# Power_Neg.net
KiCad netlist of a schematic drawn in Altium Designer
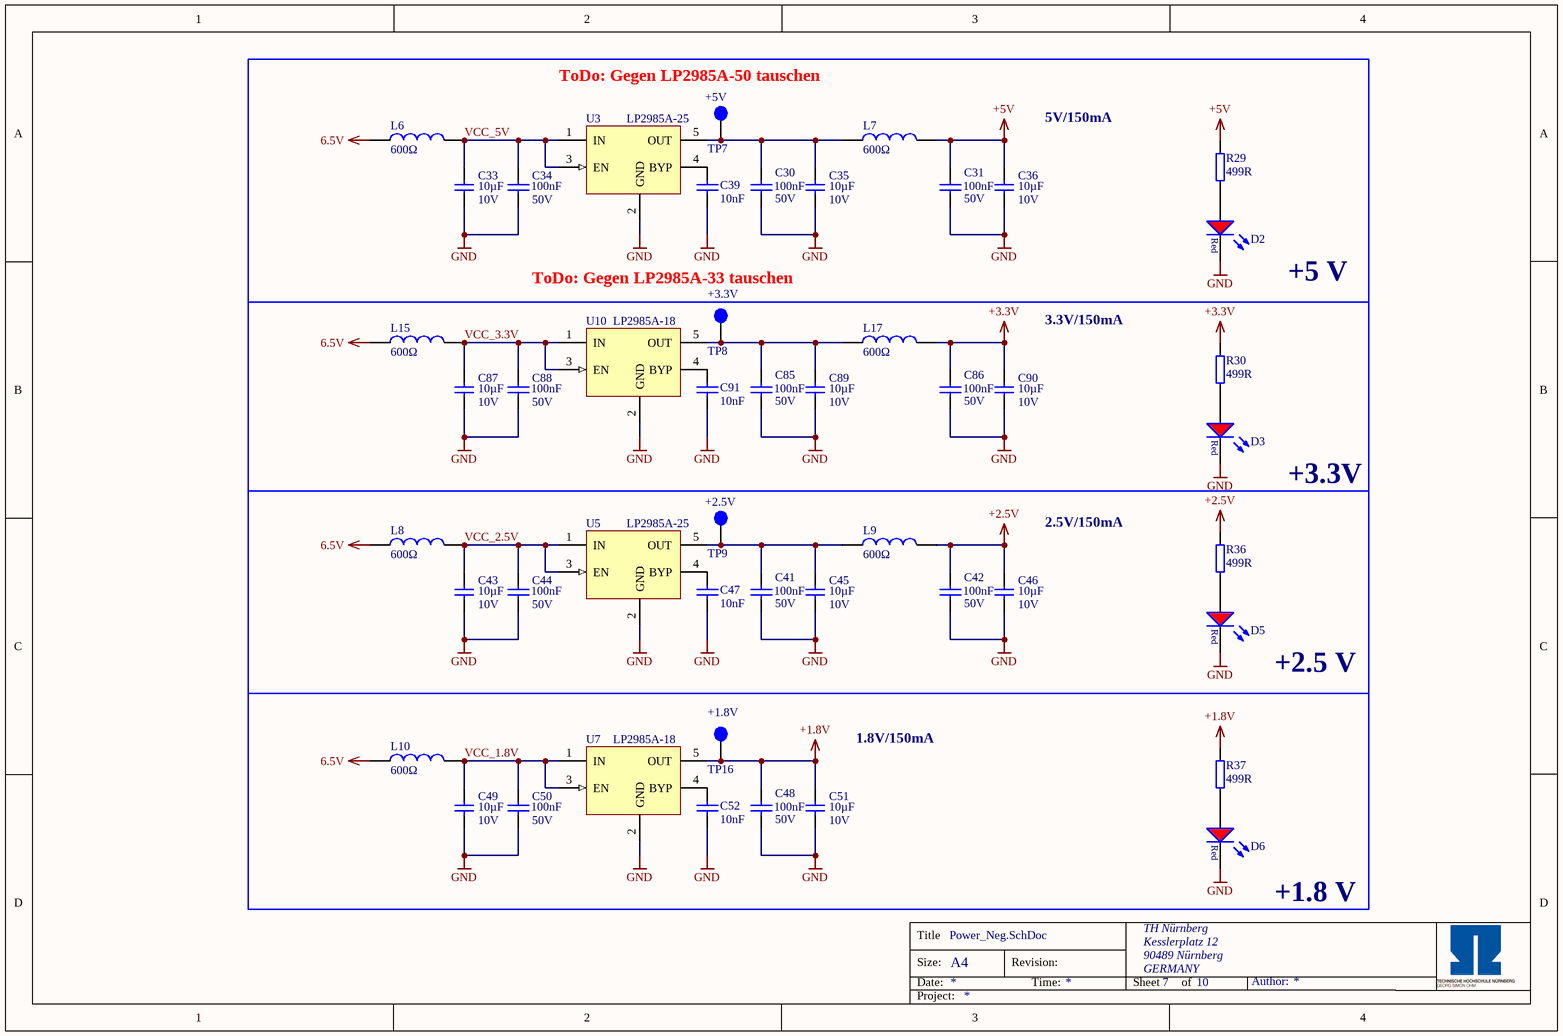
[diagram p0: Power_Neg.SchDoc]

(export (version "E")
  (design (tool "Eeschema 10.0.6"))
  (components
    (comp (ref "C30")
      (value "100nF")
      (footprint "CAPC1608X07N")
      (fields
        (field (name "MF") "Yageo")
        (field (name "MPN") "CC0603KRX7R9BB104")
        (field (name "VOLTAGE") "50V")
      )
      (libsource (lib "UltraZohm_ADC") (part "Cap_0603"))
    )
    (comp (ref "C31")
      (value "100nF")
      (footprint "CAPC1608X07N")
      (fields
        (field (name "MF") "Yageo")
        (field (name "MPN") "CC0603KRX7R9BB104")
        (field (name "VOLTAGE") "50V")
      )
      (libsource (lib "UltraZohm_ADC") (part "Cap_0603"))
    )
    (comp (ref "C33")
      (value "10µF")
      (footprint "C_1206")
      (description "Capacitor 1206")
      (fields
        (field (name "TOLERANCE") "10%")
        (field (name "MF") "Samsung Electro-Mechanics")
        (field (name "VOLTAGE") "10V")
        (field (name "CREATED") "2020_09_17_Liegmann")
      )
      (libsource (lib "UltraZohm_ADC") (part "C_1206"))
    )
    (comp (ref "C34")
      (value "100nF")
      (footprint "CAPC1608X07N")
      (fields
        (field (name "MF") "Yageo")
        (field (name "MPN") "CC0603KRX7R9BB104")
        (field (name "VOLTAGE") "50V")
        (field (name "TOLERANCE") "10%")
      )
      (libsource (lib "UltraZohm_ADC") (part "Cap_0603"))
    )
    (comp (ref "C35")
      (value "10µF")
      (footprint "C_1206")
      (description "Capacitor 1206")
      (fields
        (field (name "TOLERANCE") "10%")
        (field (name "MF") "Samsung Electro-Mechanics")
        (field (name "VOLTAGE") "10V")
        (field (name "CREATED") "2020_09_17_Liegmann")
      )
      (libsource (lib "UltraZohm_ADC") (part "C_1206"))
    )
    (comp (ref "C36")
      (value "10µF")
      (footprint "C_1206")
      (description "Capacitor 1206")
      (fields
        (field (name "TOLERANCE") "10%")
        (field (name "MF") "Samsung Electro-Mechanics")
        (field (name "VOLTAGE") "10V")
        (field (name "CREATED") "2020_09_17_Liegmann")
      )
      (libsource (lib "UltraZohm_ADC") (part "C_1206"))
    )
    (comp (ref "C39")
      (value "10nF")
      (footprint "CAPC1608X07N")
      (fields (field (name "MF") "Würth") (field (name "MPN") "885012206065") (field (name "VOLTAGE") "25V"))
      (libsource (lib "UltraZohm_ADC") (part "Cap_0603"))
    )
    (comp (ref "C41")
      (value "100nF")
      (footprint "CAPC1608X07N")
      (fields
        (field (name "MF") "Yageo")
        (field (name "MPN") "CC0603KRX7R9BB104")
        (field (name "VOLTAGE") "50V")
      )
      (libsource (lib "UltraZohm_ADC") (part "Cap_0603"))
    )
    (comp (ref "C42")
      (value "100nF")
      (footprint "CAPC1608X07N")
      (fields
        (field (name "MF") "Yageo")
        (field (name "MPN") "CC0603KRX7R9BB104")
        (field (name "VOLTAGE") "50V")
      )
      (libsource (lib "UltraZohm_ADC") (part "Cap_0603"))
    )
    (comp (ref "C43")
      (value "10µF")
      (footprint "C_1206")
      (description "Capacitor 1206")
      (fields
        (field (name "TOLERANCE") "10%")
        (field (name "MF") "Samsung Electro-Mechanics")
        (field (name "VOLTAGE") "10V")
        (field (name "CREATED") "2020_09_17_Liegmann")
      )
      (libsource (lib "UltraZohm_ADC") (part "C_1206"))
    )
    (comp (ref "C44")
      (value "100nF")
      (footprint "CAPC1608X07N")
      (fields
        (field (name "MF") "Yageo")
        (field (name "MPN") "CC0603KRX7R9BB104")
        (field (name "VOLTAGE") "50V")
        (field (name "TOLERANCE") "10%")
      )
      (libsource (lib "UltraZohm_ADC") (part "Cap_0603"))
    )
    (comp (ref "C45")
      (value "10µF")
      (footprint "C_1206")
      (description "Capacitor 1206")
      (fields
        (field (name "TOLERANCE") "10%")
        (field (name "MF") "Samsung Electro-Mechanics")
        (field (name "VOLTAGE") "10V")
        (field (name "CREATED") "2020_09_17_Liegmann")
      )
      (libsource (lib "UltraZohm_ADC") (part "C_1206"))
    )
    (comp (ref "C46")
      (value "10µF")
      (footprint "C_1206")
      (description "Capacitor 1206")
      (fields
        (field (name "TOLERANCE") "10%")
        (field (name "MF") "Samsung Electro-Mechanics")
        (field (name "VOLTAGE") "10V")
        (field (name "CREATED") "2020_09_17_Liegmann")
      )
      (libsource (lib "UltraZohm_ADC") (part "C_1206"))
    )
    (comp (ref "C47")
      (value "10nF")
      (footprint "CAPC1608X07N")
      (fields (field (name "MF") "Würth") (field (name "MPN") "885012206065") (field (name "VOLTAGE") "25V"))
      (libsource (lib "UltraZohm_ADC") (part "Cap_0603"))
    )
    (comp (ref "C48")
      (value "100nF")
      (footprint "CAPC1608X07N")
      (fields
        (field (name "MF") "Yageo")
        (field (name "MPN") "CC0603KRX7R9BB104")
        (field (name "VOLTAGE") "50V")
      )
      (libsource (lib "UltraZohm_ADC") (part "Cap_0603"))
    )
    (comp (ref "C49")
      (value "10µF")
      (footprint "C_1206")
      (description "Capacitor 1206")
      (fields
        (field (name "TOLERANCE") "10%")
        (field (name "MF") "Samsung Electro-Mechanics")
        (field (name "VOLTAGE") "10V")
        (field (name "CREATED") "2020_09_17_Liegmann")
      )
      (libsource (lib "UltraZohm_ADC") (part "C_1206"))
    )
    (comp (ref "C50")
      (value "100nF")
      (footprint "CAPC1608X07N")
      (fields
        (field (name "MF") "Yageo")
        (field (name "MPN") "CC0603KRX7R9BB104")
        (field (name "VOLTAGE") "50V")
        (field (name "TOLERANCE") "10%")
      )
      (libsource (lib "UltraZohm_ADC") (part "Cap_0603"))
    )
    (comp (ref "C51")
      (value "10µF")
      (footprint "C_1206")
      (description "Capacitor 1206")
      (fields
        (field (name "TOLERANCE") "10%")
        (field (name "MF") "Samsung Electro-Mechanics")
        (field (name "VOLTAGE") "10V")
        (field (name "CREATED") "2020_09_17_Liegmann")
      )
      (libsource (lib "UltraZohm_ADC") (part "C_1206"))
    )
    (comp (ref "C52")
      (value "10nF")
      (footprint "CAPC1608X07N")
      (fields (field (name "MF") "Würth") (field (name "MPN") "885012206065") (field (name "VOLTAGE") "25V"))
      (libsource (lib "UltraZohm_ADC") (part "Cap_0603"))
    )
    (comp (ref "C85")
      (value "100nF")
      (footprint "CAPC1608X07N")
      (fields
        (field (name "MF") "Yageo")
        (field (name "MPN") "CC0603KRX7R9BB104")
        (field (name "VOLTAGE") "50V")
      )
      (libsource (lib "UltraZohm_ADC") (part "Cap_0603"))
    )
    (comp (ref "C86")
      (value "100nF")
      (footprint "CAPC1608X07N")
      (fields
        (field (name "MF") "Yageo")
        (field (name "MPN") "CC0603KRX7R9BB104")
        (field (name "VOLTAGE") "50V")
      )
      (libsource (lib "UltraZohm_ADC") (part "Cap_0603"))
    )
    (comp (ref "C87")
      (value "10µF")
      (footprint "C_1206")
      (description "Capacitor 1206")
      (fields
        (field (name "TOLERANCE") "10%")
        (field (name "MF") "Samsung Electro-Mechanics")
        (field (name "VOLTAGE") "10V")
        (field (name "CREATED") "2020_09_17_Liegmann")
      )
      (libsource (lib "UltraZohm_ADC") (part "C_1206"))
    )
    (comp (ref "C88")
      (value "100nF")
      (footprint "CAPC1608X07N")
      (fields
        (field (name "MF") "Yageo")
        (field (name "MPN") "CC0603KRX7R9BB104")
        (field (name "VOLTAGE") "50V")
        (field (name "TOLERANCE") "10%")
      )
      (libsource (lib "UltraZohm_ADC") (part "Cap_0603"))
    )
    (comp (ref "C89")
      (value "10µF")
      (footprint "C_1206")
      (description "Capacitor 1206")
      (fields
        (field (name "TOLERANCE") "10%")
        (field (name "MF") "Samsung Electro-Mechanics")
        (field (name "VOLTAGE") "10V")
        (field (name "CREATED") "2020_09_17_Liegmann")
      )
      (libsource (lib "UltraZohm_ADC") (part "C_1206"))
    )
    (comp (ref "C90")
      (value "10µF")
      (footprint "C_1206")
      (description "Capacitor 1206")
      (fields
        (field (name "TOLERANCE") "10%")
        (field (name "MF") "Samsung Electro-Mechanics")
        (field (name "VOLTAGE") "10V")
        (field (name "CREATED") "2020_09_17_Liegmann")
      )
      (libsource (lib "UltraZohm_ADC") (part "C_1206"))
    )
    (comp (ref "C91")
      (value "10nF")
      (footprint "CAPC1608X07N")
      (fields (field (name "MF") "Würth") (field (name "MPN") "885012206065") (field (name "VOLTAGE") "25V"))
      (libsource (lib "UltraZohm_ADC") (part "Cap_0603"))
    )
    (comp (ref "D2")
      (value "150060RS75000")
      (footprint "WL-SMCW_0603")
      (description "WL-SMCW SMD Mono-color Chip LED Waterclear, size 0603, Red, 2 V, 140°")
      (fields (field (name "MF") "Wuerth Elektronik") (field (name "CREATED") "2018_09_06_AGeiger"))
      (libsource (lib "UltraZohm_ADC") (part "LED_Red_0603"))
    )
    (comp (ref "D3")
      (value "150060RS75000")
      (footprint "WL-SMCW_0603")
      (description "WL-SMCW SMD Mono-color Chip LED Waterclear, size 0603, Red, 2 V, 140°")
      (fields (field (name "MF") "Wuerth Elektronik") (field (name "CREATED") "2018_09_06_AGeiger"))
      (libsource (lib "UltraZohm_ADC") (part "LED_Red_0603"))
    )
    (comp (ref "D5")
      (value "150060RS75000")
      (footprint "WL-SMCW_0603")
      (description "WL-SMCW SMD Mono-color Chip LED Waterclear, size 0603, Red, 2 V, 140°")
      (fields (field (name "MF") "Wuerth Elektronik") (field (name "CREATED") "2018_09_06_AGeiger"))
      (libsource (lib "UltraZohm_ADC") (part "LED_Red_0603"))
    )
    (comp (ref "D6")
      (value "150060RS75000")
      (footprint "WL-SMCW_0603")
      (description "WL-SMCW SMD Mono-color Chip LED Waterclear, size 0603, Red, 2 V, 140°")
      (fields (field (name "MF") "Wuerth Elektronik") (field (name "CREATED") "2018_09_06_AGeiger"))
      (libsource (lib "UltraZohm_ADC") (part "LED_Red_0603"))
    )
    (comp (ref "L6")
      (value "600Ω")
      (footprint "WE-CBF_0805_High Current")
      (description "WE-CBF SMD EMI Suppression Ferrite Bead, 0805, 600Ω")
      (fields (field (name "MF") "Wurth Elektronik") (field (name "MPN") "742792040"))
      (libsource (lib "UltraZohm_ADC") (part "WE-CBF, 742792040"))
    )
    (comp (ref "L7")
      (value "600Ω")
      (footprint "WE-CBF_0805_High Current")
      (description "WE-CBF SMD EMI Suppression Ferrite Bead, 0805, 600Ω")
      (fields (field (name "MF") "Wurth Elektronik") (field (name "MPN") "742792040"))
      (libsource (lib "UltraZohm_ADC") (part "WE-CBF, 742792040"))
    )
    (comp (ref "L8")
      (value "600Ω")
      (footprint "WE-CBF_0805_High Current")
      (description "WE-CBF SMD EMI Suppression Ferrite Bead, 0805, 600Ω")
      (fields (field (name "MF") "Wurth Elektronik") (field (name "MPN") "742792040"))
      (libsource (lib "UltraZohm_ADC") (part "WE-CBF, 742792040"))
    )
    (comp (ref "L9")
      (value "600Ω")
      (footprint "WE-CBF_0805_High Current")
      (description "WE-CBF SMD EMI Suppression Ferrite Bead, 0805, 600Ω")
      (fields (field (name "MF") "Wurth Elektronik") (field (name "MPN") "742792040"))
      (libsource (lib "UltraZohm_ADC") (part "WE-CBF, 742792040"))
    )
    (comp (ref "L10")
      (value "600Ω")
      (footprint "WE-CBF_0805_High Current")
      (description "WE-CBF SMD EMI Suppression Ferrite Bead, 0805, 600Ω")
      (fields (field (name "MF") "Wurth Elektronik") (field (name "MPN") "742792040"))
      (libsource (lib "UltraZohm_ADC") (part "WE-CBF, 742792040"))
    )
    (comp (ref "L15")
      (value "600Ω")
      (footprint "WE-CBF_0805_High Current")
      (description "WE-CBF SMD EMI Suppression Ferrite Bead, 0805, 600Ω")
      (fields (field (name "MF") "Wurth Elektronik") (field (name "MPN") "742792040"))
      (libsource (lib "UltraZohm_ADC") (part "WE-CBF, 742792040"))
    )
    (comp (ref "L17")
      (value "600Ω")
      (footprint "WE-CBF_0805_High Current")
      (description "WE-CBF SMD EMI Suppression Ferrite Bead, 0805, 600Ω")
      (fields (field (name "MF") "Wurth Elektronik") (field (name "MPN") "742792040"))
      (libsource (lib "UltraZohm_ADC") (part "WE-CBF, 742792040"))
    )
    (comp (ref "R29")
      (value "499R")
      (footprint "RESC1608X06N")
      (fields (field (name "MF") "Vishay / Dale") (field (name "MPN") "CRCW0603499RFKEAC"))
      (libsource (lib "UltraZohm_ADC") (part "R_0603"))
    )
    (comp (ref "R30")
      (value "499R")
      (footprint "RESC1608X06N")
      (fields (field (name "MF") "Vishay / Dale") (field (name "MPN") "CRCW0603499RFKEAC"))
      (libsource (lib "UltraZohm_ADC") (part "R_0603"))
    )
    (comp (ref "R36")
      (value "499R")
      (footprint "RESC1608X06N")
      (fields (field (name "MF") "Vishay / Dale") (field (name "MPN") "CRCW0603499RFKEAC"))
      (libsource (lib "UltraZohm_ADC") (part "R_0603"))
    )
    (comp (ref "R37")
      (value "499R")
      (footprint "RESC1608X06N")
      (fields (field (name "MF") "Vishay / Dale") (field (name "MPN") "CRCW0603499RFKEAC"))
      (libsource (lib "UltraZohm_ADC") (part "R_0603"))
    )
    (comp (ref "TP7")
      (value "+5V")
      (footprint "TP_1mm")
      (description "Testpoint 1mm")
      (fields (field (name "CREATED") "2018_06_25_AGeiger"))
      (libsource (lib "UltraZOhm_CarrierBoard") (part "TP_1mm"))
    )
    (comp (ref "TP8")
      (value "+3.3V")
      (footprint "TP_1mm")
      (description "Testpoint 1mm")
      (fields (field (name "CREATED") "2018_06_25_AGeiger"))
      (libsource (lib "UltraZOhm_CarrierBoard") (part "TP_1mm"))
    )
    (comp (ref "TP9")
      (value "+2.5V")
      (footprint "TP_1mm")
      (description "Testpoint 1mm")
      (fields (field (name "CREATED") "2018_06_25_AGeiger"))
      (libsource (lib "UltraZOhm_CarrierBoard") (part "TP_1mm"))
    )
    (comp (ref "TP16")
      (value "+1.8V")
      (footprint "TP_1mm")
      (description "Testpoint 1mm")
      (fields (field (name "CREATED") "2018_06_25_AGeiger"))
      (libsource (lib "UltraZOhm_CarrierBoard") (part "TP_1mm"))
    )
    (comp (ref "U3")
      (value "LP2985A-25")
      (footprint "SOT95P250X110-5N")
      (description "150mA, LDO, Vout = 2.5V, Vin,max = 16V")
      (fields (field (name "MF") "Texas Instruments"))
      (libsource (lib "UltraZohm_ADC") (part "LP2985A-25"))
    )
    (comp (ref "U5")
      (value "LP2985A-25")
      (footprint "SOT95P250X110-5N")
      (description "150mA, LDO, Vout = 2.5V, Vin,max = 16V")
      (fields (field (name "MF") "Texas Instruments"))
      (libsource (lib "UltraZohm_ADC") (part "LP2985A-25"))
    )
    (comp (ref "U7")
      (value "LP2985A-18")
      (footprint "SOT95P250X110-5N")
      (description "150mA, LDO, Vout = 1.8V , Vin,max = 16V")
      (libsource (lib "UltraZohm_ADC") (part "LP2985A-18"))
    )
    (comp (ref "U10")
      (value "LP2985A-18")
      (footprint "SOT95P250X110-5N")
      (description "150mA, LDO, Vout = 1.8V , Vin,max = 16V")
      (libsource (lib "UltraZohm_ADC") (part "LP2985A-18"))
    )
  )
  (nets
    (net (code "1") (name "+1.8V") (class "Default")
      (node (ref "C48") (pin "1") (pinfunction "1_1") (pintype "passive"))
      (node (ref "C51") (pin "2") (pinfunction "2_2") (pintype "passive"))
      (node (ref "R37") (pin "2") (pintype "passive"))
      (node (ref "TP16") (pin "1") (pintype "passive"))
      (node (ref "U7") (pin "5") (pinfunction "OUT_5") (pintype "power_in"))
    )
    (net (code "2") (name "+2.5V") (class "Default")
      (node (ref "C42") (pin "1") (pinfunction "1_1") (pintype "passive"))
      (node (ref "C46") (pin "2") (pinfunction "2_2") (pintype "passive"))
      (node (ref "L9") (pin "2") (pinfunction "2_2") (pintype "passive"))
      (node (ref "R36") (pin "2") (pintype "passive"))
    )
    (net (code "3") (name "+3.3V") (class "Default")
      (node (ref "C86") (pin "1") (pinfunction "1_1") (pintype "passive"))
      (node (ref "C90") (pin "2") (pinfunction "2_2") (pintype "passive"))
      (node (ref "L17") (pin "2") (pinfunction "2_2") (pintype "passive"))
      (node (ref "R30") (pin "2") (pintype "passive"))
    )
    (net (code "4") (name "+5V") (class "Default")
      (node (ref "C31") (pin "1") (pinfunction "1_1") (pintype "passive"))
      (node (ref "C36") (pin "2") (pinfunction "2_2") (pintype "passive"))
      (node (ref "L7") (pin "2") (pinfunction "2_2") (pintype "passive"))
      (node (ref "R29") (pin "2") (pintype "passive"))
    )
    (net (code "5") (name "/VCC_1.8V") (class "Default")
      (node (ref "C49") (pin "2") (pinfunction "2_2") (pintype "passive"))
      (node (ref "C50") (pin "1") (pinfunction "1_1") (pintype "passive"))
      (node (ref "L10") (pin "2") (pinfunction "2_2") (pintype "passive"))
      (node (ref "U7") (pin "1") (pinfunction "IN_1") (pintype "power_in"))
      (node (ref "U7") (pin "3") (pinfunction "EN_3") (pintype "input"))
    )
    (net (code "6") (name "/VCC_2.5V") (class "Default")
      (node (ref "C43") (pin "2") (pinfunction "2_2") (pintype "passive"))
      (node (ref "C44") (pin "1") (pinfunction "1_1") (pintype "passive"))
      (node (ref "L8") (pin "2") (pinfunction "2_2") (pintype "passive"))
      (node (ref "U5") (pin "1") (pinfunction "IN_1") (pintype "power_in"))
      (node (ref "U5") (pin "3") (pinfunction "EN_3") (pintype "input"))
    )
    (net (code "7") (name "/VCC_3.3V") (class "Default")
      (node (ref "C87") (pin "2") (pinfunction "2_2") (pintype "passive"))
      (node (ref "C88") (pin "1") (pinfunction "1_1") (pintype "passive"))
      (node (ref "L15") (pin "2") (pinfunction "2_2") (pintype "passive"))
      (node (ref "U10") (pin "1") (pinfunction "IN_1") (pintype "power_in"))
      (node (ref "U10") (pin "3") (pinfunction "EN_3") (pintype "input"))
    )
    (net (code "8") (name "/VCC_5V") (class "Default")
      (node (ref "C33") (pin "2") (pinfunction "2_2") (pintype "passive"))
      (node (ref "C34") (pin "1") (pinfunction "1_1") (pintype "passive"))
      (node (ref "L6") (pin "2") (pinfunction "2_2") (pintype "passive"))
      (node (ref "U3") (pin "1") (pinfunction "IN_1") (pintype "power_in"))
      (node (ref "U3") (pin "3") (pinfunction "EN_3") (pintype "input"))
    )
    (net (code "9") (name "6.5V") (class "Default")
      (node (ref "L10") (pin "1") (pinfunction "1_1") (pintype "passive"))
      (node (ref "L15") (pin "1") (pinfunction "1_1") (pintype "passive"))
      (node (ref "L6") (pin "1") (pinfunction "1_1") (pintype "passive"))
      (node (ref "L8") (pin "1") (pinfunction "1_1") (pintype "passive"))
    )
    (net (code "10") (name "GND") (class "Default")
      (node (ref "C30") (pin "2") (pinfunction "2_2") (pintype "passive"))
      (node (ref "C31") (pin "2") (pinfunction "2_2") (pintype "passive"))
      (node (ref "C33") (pin "1") (pinfunction "1_1") (pintype "passive"))
      (node (ref "C34") (pin "2") (pinfunction "2_2") (pintype "passive"))
      (node (ref "C35") (pin "1") (pinfunction "1_1") (pintype "passive"))
      (node (ref "C36") (pin "1") (pinfunction "1_1") (pintype "passive"))
      (node (ref "C39") (pin "1") (pinfunction "1_1") (pintype "passive"))
      (node (ref "C41") (pin "2") (pinfunction "2_2") (pintype "passive"))
      (node (ref "C42") (pin "2") (pinfunction "2_2") (pintype "passive"))
      (node (ref "C43") (pin "1") (pinfunction "1_1") (pintype "passive"))
      (node (ref "C44") (pin "2") (pinfunction "2_2") (pintype "passive"))
      (node (ref "C45") (pin "1") (pinfunction "1_1") (pintype "passive"))
      (node (ref "C46") (pin "1") (pinfunction "1_1") (pintype "passive"))
      (node (ref "C47") (pin "1") (pinfunction "1_1") (pintype "passive"))
      (node (ref "C48") (pin "2") (pinfunction "2_2") (pintype "passive"))
      (node (ref "C49") (pin "1") (pinfunction "1_1") (pintype "passive"))
      (node (ref "C50") (pin "2") (pinfunction "2_2") (pintype "passive"))
      (node (ref "C51") (pin "1") (pinfunction "1_1") (pintype "passive"))
      (node (ref "C52") (pin "1") (pinfunction "1_1") (pintype "passive"))
      (node (ref "C85") (pin "2") (pinfunction "2_2") (pintype "passive"))
      (node (ref "C86") (pin "2") (pinfunction "2_2") (pintype "passive"))
      (node (ref "C87") (pin "1") (pinfunction "1_1") (pintype "passive"))
      (node (ref "C88") (pin "2") (pinfunction "2_2") (pintype "passive"))
      (node (ref "C89") (pin "1") (pinfunction "1_1") (pintype "passive"))
      (node (ref "C90") (pin "1") (pinfunction "1_1") (pintype "passive"))
      (node (ref "C91") (pin "1") (pinfunction "1_1") (pintype "passive"))
      (node (ref "D2") (pin "1") (pinfunction "K_1") (pintype "passive"))
      (node (ref "D3") (pin "1") (pinfunction "K_1") (pintype "passive"))
      (node (ref "D5") (pin "1") (pinfunction "K_1") (pintype "passive"))
      (node (ref "D6") (pin "1") (pinfunction "K_1") (pintype "passive"))
      (node (ref "U10") (pin "2") (pinfunction "GND_2") (pintype "power_in"))
      (node (ref "U3") (pin "2") (pinfunction "GND_2") (pintype "power_in"))
      (node (ref "U5") (pin "2") (pinfunction "GND_2") (pintype "power_in"))
      (node (ref "U7") (pin "2") (pinfunction "GND_2") (pintype "power_in"))
    )
    (net (code "11") (name "Net-(D2-A)") (class "Default")
      (node (ref "D2") (pin "2") (pinfunction "A_2") (pintype "passive"))
      (node (ref "R29") (pin "1") (pintype "passive"))
    )
    (net (code "12") (name "Net-(D3-A)") (class "Default")
      (node (ref "D3") (pin "2") (pinfunction "A_2") (pintype "passive"))
      (node (ref "R30") (pin "1") (pintype "passive"))
    )
    (net (code "13") (name "Net-(D5-A)") (class "Default")
      (node (ref "D5") (pin "2") (pinfunction "A_2") (pintype "passive"))
      (node (ref "R36") (pin "1") (pintype "passive"))
    )
    (net (code "14") (name "Net-(D6-A)") (class "Default")
      (node (ref "D6") (pin "2") (pinfunction "A_2") (pintype "passive"))
      (node (ref "R37") (pin "1") (pintype "passive"))
    )
    (net (code "15") (name "Net-(U3-BYP)") (class "Default")
      (node (ref "C39") (pin "2") (pinfunction "2_2") (pintype "passive"))
      (node (ref "U3") (pin "4") (pinfunction "BYP_4") (pintype "passive"))
    )
    (net (code "16") (name "Net-(U3-OUT)") (class "Default")
      (node (ref "C30") (pin "1") (pinfunction "1_1") (pintype "passive"))
      (node (ref "C35") (pin "2") (pinfunction "2_2") (pintype "passive"))
      (node (ref "L7") (pin "1") (pinfunction "1_1") (pintype "passive"))
      (node (ref "TP7") (pin "1") (pintype "passive"))
      (node (ref "U3") (pin "5") (pinfunction "OUT_5") (pintype "power_in"))
    )
    (net (code "17") (name "Net-(U5-BYP)") (class "Default")
      (node (ref "C47") (pin "2") (pinfunction "2_2") (pintype "passive"))
      (node (ref "U5") (pin "4") (pinfunction "BYP_4") (pintype "passive"))
    )
    (net (code "18") (name "Net-(U5-OUT)") (class "Default")
      (node (ref "C41") (pin "1") (pinfunction "1_1") (pintype "passive"))
      (node (ref "C45") (pin "2") (pinfunction "2_2") (pintype "passive"))
      (node (ref "L9") (pin "1") (pinfunction "1_1") (pintype "passive"))
      (node (ref "TP9") (pin "1") (pintype "passive"))
      (node (ref "U5") (pin "5") (pinfunction "OUT_5") (pintype "power_in"))
    )
    (net (code "19") (name "Net-(U7-BYP)") (class "Default")
      (node (ref "C52") (pin "2") (pinfunction "2_2") (pintype "passive"))
      (node (ref "U7") (pin "4") (pinfunction "BYP_4") (pintype "passive"))
    )
    (net (code "20") (name "Net-(U10-BYP)") (class "Default")
      (node (ref "C91") (pin "2") (pinfunction "2_2") (pintype "passive"))
      (node (ref "U10") (pin "4") (pinfunction "BYP_4") (pintype "passive"))
    )
    (net (code "21") (name "Net-(U10-OUT)") (class "Default")
      (node (ref "C85") (pin "1") (pinfunction "1_1") (pintype "passive"))
      (node (ref "C89") (pin "2") (pinfunction "2_2") (pintype "passive"))
      (node (ref "L17") (pin "1") (pinfunction "1_1") (pintype "passive"))
      (node (ref "TP8") (pin "1") (pintype "passive"))
      (node (ref "U10") (pin "5") (pinfunction "OUT_5") (pintype "power_in"))
    )
  )
)
